# EEPROM.net
KiCad netlist of a schematic drawn in Altium Designer
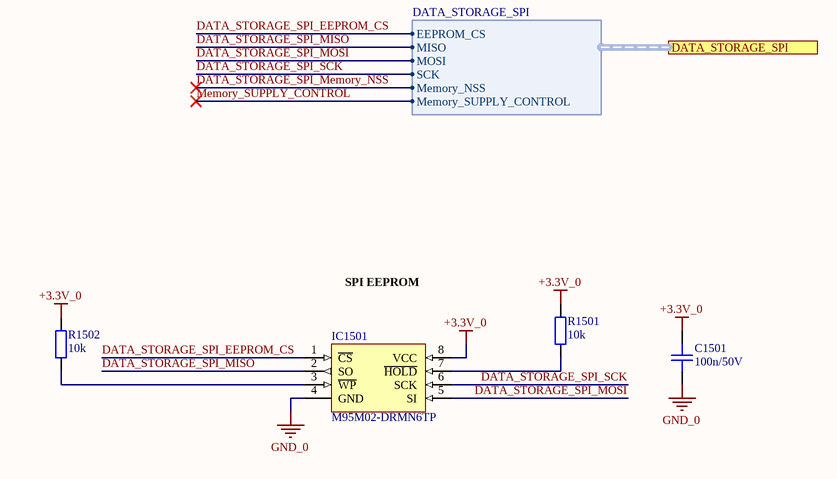
[diagram p0: EEPROM.SchDoc]

(export (version "E")
  (design (tool "Eeschema 10.0.6"))
  (components
    (comp (ref "C1501")
      (value "100n/50V")
      (footprint "CAPC1608X08N")
      (description "MLCC")
      (fields (field (name "PART NUMBER") "gen_C_ceramic_100n_50V_X7R_0603"))
      (libsource (lib "OE750") (part "C"))
    )
    (comp (ref "IC1501")
      (value "M95M02-DRMN6TP")
      (footprint "SOIC127P600X175-8N")
      (description "2-Mbit serial SPI bus EEPROM")
      (fields (field (name "MANUFACTURER") "StMicroelectronics"))
      (libsource (lib "OE750") (part "gen_EEPROM_SPI_8Pin"))
    )
    (comp (ref "R1501")
      (value "10k")
      (footprint "RESC1608X05N")
      (description "SMD Resistor 10k 0603")
      (fields (field (name "PART NUMBER") "gen_R_10k_0603") (field (name "TOLERANCE") "1%"))
      (libsource (lib "OE750") (part "R"))
    )
    (comp (ref "R1502")
      (value "10k")
      (footprint "RESC1608X05N")
      (description "SMD Resistor 10k 0603")
      (fields (field (name "PART NUMBER") "gen_R_10k_0603") (field (name "TOLERANCE") "1%"))
      (libsource (lib "OE750") (part "R"))
    )
  )
  (nets
    (net (code "2") (name "+3.3V_0") (class "Default")
      (node (ref "C1501") (pin "2") (pinfunction "2_2") (pintype "passive"))
      (node (ref "IC1501") (pin "8") (pinfunction "VCC_8") (pintype "input"))
      (node (ref "R1501") (pin "2") (pinfunction "2_2") (pintype "passive"))
      (node (ref "R1502") (pin "2") (pinfunction "2_2") (pintype "passive"))
    )
    (net (code "3") (name "/DATA_STORAGE_SPI_EEPROM_CS") (class "Default")
      (node (ref "IC1501") (pin "1") (pinfunction "~{CS}_1") (pintype "input"))
    )
    (net (code "4") (name "/DATA_STORAGE_SPI_MISO") (class "Default")
      (node (ref "IC1501") (pin "2") (pinfunction "SO_2") (pintype "output"))
    )
    (net (code "5") (name "/DATA_STORAGE_SPI_MOSI") (class "Default")
      (node (ref "IC1501") (pin "5") (pinfunction "SI_5") (pintype "input"))
    )
    (net (code "7") (name "/DATA_STORAGE_SPI_SCK") (class "Default")
      (node (ref "IC1501") (pin "6") (pinfunction "SCK_6") (pintype "input"))
    )
    (net (code "10") (name "GND_0") (class "Default")
      (node (ref "C1501") (pin "1") (pinfunction "1_1") (pintype "passive"))
      (node (ref "IC1501") (pin "4") (pinfunction "GND_4") (pintype "power_in"))
    )
    (net (code "11") (name "Net-(IC1501-~{HOLD})") (class "Default")
      (node (ref "IC1501") (pin "7") (pinfunction "~{HOLD}_7") (pintype "input"))
      (node (ref "R1501") (pin "1") (pinfunction "1_1") (pintype "passive"))
    )
    (net (code "12") (name "Net-(IC1501-~{WP})") (class "Default")
      (node (ref "IC1501") (pin "3") (pinfunction "~{WP}_3") (pintype "input"))
      (node (ref "R1502") (pin "1") (pinfunction "1_1") (pintype "passive"))
    )
  )
)
